# tempPCB.net
KiCad netlist of a schematic drawn in EAGLE
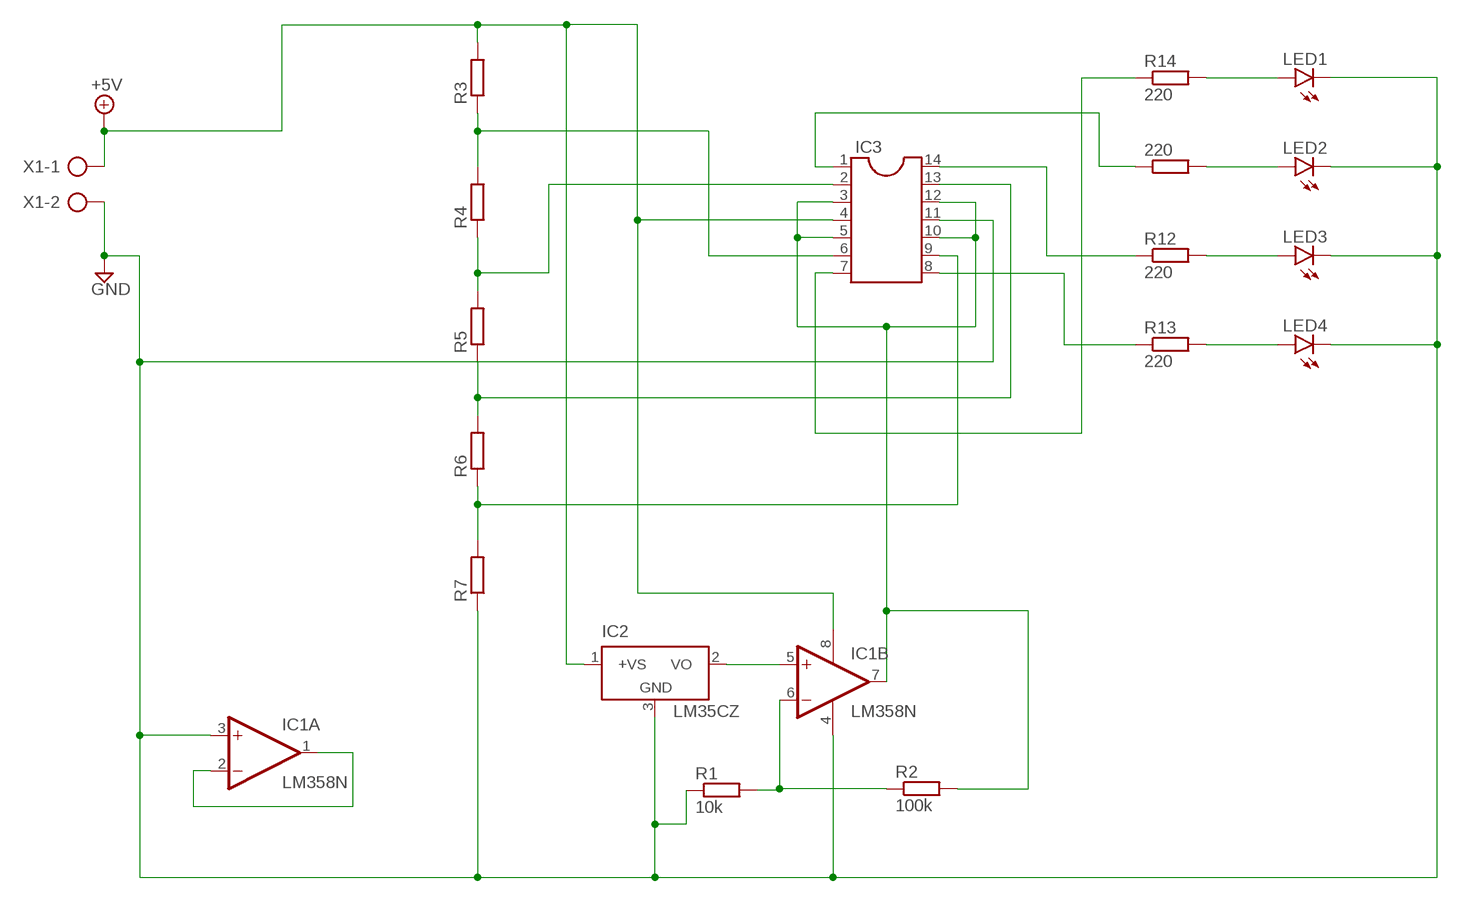
[diagram p0: schematic, sheet 1]

(export (version "E")
  (design (tool "Eeschema 10.0.6"))
  (components
    (comp (ref "220")
      (value "R-EU_0207/10")
      (footprint "eagle-import:0207_10")
      (libsource (lib "eagle-import") (part "R-EU_0207/10"))
    )
    (comp (ref "IC1")
      (value "LM358N")
      (footprint "eagle-import:DIL08")
      (libsource (lib "eagle-import") (part "LM358N"))
    )
    (comp (ref "IC2")
      (value "LM35CZ")
      (footprint "eagle-import:TO92")
      (libsource (lib "eagle-import") (part "LM35CZ"))
    )
    (comp (ref "IC3")
      (value "DIL14")
      (footprint "eagle-import:DIL14")
      (libsource (lib "eagle-import") (part "DIL14"))
    )
    (comp (ref "LED1")
      (value "LED5MM")
      (footprint "eagle-import:LED5MM")
      (libsource (lib "eagle-import") (part "LED5MM"))
    )
    (comp (ref "LED2")
      (value "LED5MM")
      (footprint "eagle-import:LED5MM")
      (libsource (lib "eagle-import") (part "LED5MM"))
    )
    (comp (ref "LED3")
      (value "LED5MM")
      (footprint "eagle-import:LED5MM")
      (libsource (lib "eagle-import") (part "LED5MM"))
    )
    (comp (ref "LED4")
      (value "LED5MM")
      (footprint "eagle-import:LED5MM")
      (libsource (lib "eagle-import") (part "LED5MM"))
    )
    (comp (ref "R1")
      (value "10k")
      (footprint "eagle-import:R1206")
      (libsource (lib "eagle-import") (part "R-EU_R1206"))
    )
    (comp (ref "R2")
      (value "100k")
      (footprint "eagle-import:R1206")
      (libsource (lib "eagle-import") (part "R-EU_R1206"))
    )
    (comp (ref "R3")
      (value "R-EU_R1206")
      (footprint "eagle-import:R1206")
      (libsource (lib "eagle-import") (part "R-EU_R1206"))
    )
    (comp (ref "R4")
      (value "R-EU_0207/10")
      (footprint "eagle-import:0207_10")
      (libsource (lib "eagle-import") (part "R-EU_0207/10"))
    )
    (comp (ref "R5")
      (value "R-EU_R1206")
      (footprint "eagle-import:R1206")
      (libsource (lib "eagle-import") (part "R-EU_R1206"))
    )
    (comp (ref "R6")
      (value "R-EU_0207/10")
      (footprint "eagle-import:0207_10")
      (libsource (lib "eagle-import") (part "R-EU_0207/10"))
    )
    (comp (ref "R7")
      (value "R-EU_R1206")
      (footprint "eagle-import:R1206")
      (libsource (lib "eagle-import") (part "R-EU_R1206"))
    )
    (comp (ref "R12")
      (value "220")
      (footprint "eagle-import:0207_10")
      (libsource (lib "eagle-import") (part "R-EU_0207/10"))
    )
    (comp (ref "R13")
      (value "220")
      (footprint "eagle-import:0207_10")
      (libsource (lib "eagle-import") (part "R-EU_0207/10"))
    )
    (comp (ref "R14")
      (value "220")
      (footprint "eagle-import:0207_10")
      (libsource (lib "eagle-import") (part "R-EU_0207/10"))
    )
    (comp (ref "X1")
      (value "AK500/2")
      (footprint "eagle-import:AK500_2")
      (libsource (lib "eagle-import") (part "AK500/2"))
    )
  )
  (nets
    (net (code "1") (name "+5V") (class "Default")
      (node (ref "IC1") (pin "8") (pinfunction "V+_8") (pintype "power_in"))
      (node (ref "IC2") (pin "1") (pinfunction "+VS_1") (pintype "input"))
      (node (ref "IC3") (pin "4") (pinfunction "4_4") (pintype "passive"))
      (node (ref "R3") (pin "2") (pinfunction "2_2") (pintype "passive"))
      (node (ref "X1") (pin "1") (pinfunction "KL_1") (pintype "passive"))
    )
    (net (code "2") (name "GND") (class "Default")
      (node (ref "IC1") (pin "3") (pinfunction "+IN_3") (pintype "input"))
      (node (ref "IC1") (pin "4") (pinfunction "V-_4") (pintype "power_in"))
      (node (ref "IC2") (pin "3") (pinfunction "GND_3") (pintype "power_in"))
      (node (ref "IC3") (pin "11") (pinfunction "11_11") (pintype "passive"))
      (node (ref "LED1") (pin "K") (pinfunction "C_K") (pintype "passive"))
      (node (ref "LED2") (pin "K") (pinfunction "C_K") (pintype "passive"))
      (node (ref "LED3") (pin "K") (pinfunction "C_K") (pintype "passive"))
      (node (ref "LED4") (pin "K") (pinfunction "C_K") (pintype "passive"))
      (node (ref "R1") (pin "1") (pinfunction "1_1") (pintype "passive"))
      (node (ref "R7") (pin "1") (pinfunction "1_1") (pintype "passive"))
      (node (ref "X1") (pin "2") (pinfunction "KL_2") (pintype "passive"))
    )
    (net (code "3") (name "Net-(220-Pad1)") (class "Default")
      (node (ref "220") (pin "1") (pinfunction "1_1") (pintype "passive"))
      (node (ref "IC3") (pin "1") (pinfunction "1_1") (pintype "passive"))
    )
    (net (code "4") (name "Net-(220-Pad2)") (class "Default")
      (node (ref "220") (pin "2") (pinfunction "2_2") (pintype "passive"))
      (node (ref "LED2") (pin "A") (pinfunction "A_A") (pintype "passive"))
    )
    (net (code "5") (name "Net-(IC1A--IN)") (class "Default")
      (node (ref "IC1") (pin "1") (pinfunction "OUT_1") (pintype "output"))
      (node (ref "IC1") (pin "2") (pinfunction "-IN_2") (pintype "input"))
    )
    (net (code "6") (name "Net-(IC1B-+IN)") (class "Default")
      (node (ref "IC1") (pin "5") (pinfunction "+IN_5") (pintype "input"))
      (node (ref "IC2") (pin "2") (pinfunction "VO_2") (pintype "input"))
    )
    (net (code "7") (name "Net-(IC1B--IN)") (class "Default")
      (node (ref "IC1") (pin "6") (pinfunction "-IN_6") (pintype "input"))
      (node (ref "R1") (pin "2") (pinfunction "2_2") (pintype "passive"))
      (node (ref "R2") (pin "1") (pinfunction "1_1") (pintype "passive"))
    )
    (net (code "8") (name "Net-(IC1B-OUT)") (class "Default")
      (node (ref "IC1") (pin "7") (pinfunction "OUT_7") (pintype "output"))
      (node (ref "IC3") (pin "10") (pinfunction "10_10") (pintype "passive"))
      (node (ref "IC3") (pin "12") (pinfunction "12_12") (pintype "passive"))
      (node (ref "IC3") (pin "3") (pinfunction "3_3") (pintype "passive"))
      (node (ref "IC3") (pin "5") (pinfunction "5_5") (pintype "passive"))
      (node (ref "R2") (pin "2") (pinfunction "2_2") (pintype "passive"))
    )
    (net (code "9") (name "Net-(IC3-Pad2)") (class "Default")
      (node (ref "IC3") (pin "2") (pinfunction "2_2") (pintype "passive"))
      (node (ref "R4") (pin "1") (pinfunction "1_1") (pintype "passive"))
      (node (ref "R5") (pin "2") (pinfunction "2_2") (pintype "passive"))
    )
    (net (code "10") (name "Net-(IC3-Pad6)") (class "Default")
      (node (ref "IC3") (pin "6") (pinfunction "6_6") (pintype "passive"))
      (node (ref "R3") (pin "1") (pinfunction "1_1") (pintype "passive"))
      (node (ref "R4") (pin "2") (pinfunction "2_2") (pintype "passive"))
    )
    (net (code "11") (name "Net-(IC3-Pad7)") (class "Default")
      (node (ref "IC3") (pin "7") (pinfunction "7_7") (pintype "passive"))
      (node (ref "R14") (pin "1") (pinfunction "1_1") (pintype "passive"))
    )
    (net (code "12") (name "Net-(IC3-Pad8)") (class "Default")
      (node (ref "IC3") (pin "8") (pinfunction "8_8") (pintype "passive"))
      (node (ref "R13") (pin "1") (pinfunction "1_1") (pintype "passive"))
    )
    (net (code "13") (name "Net-(IC3-Pad9)") (class "Default")
      (node (ref "IC3") (pin "9") (pinfunction "9_9") (pintype "passive"))
      (node (ref "R6") (pin "1") (pinfunction "1_1") (pintype "passive"))
      (node (ref "R7") (pin "2") (pinfunction "2_2") (pintype "passive"))
    )
    (net (code "14") (name "Net-(IC3-Pad13)") (class "Default")
      (node (ref "IC3") (pin "13") (pinfunction "13_13") (pintype "passive"))
      (node (ref "R5") (pin "1") (pinfunction "1_1") (pintype "passive"))
      (node (ref "R6") (pin "2") (pinfunction "2_2") (pintype "passive"))
    )
    (net (code "15") (name "Net-(IC3-Pad14)") (class "Default")
      (node (ref "IC3") (pin "14") (pinfunction "14_14") (pintype "passive"))
      (node (ref "R12") (pin "1") (pinfunction "1_1") (pintype "passive"))
    )
    (net (code "16") (name "Net-(LED1-PadA)") (class "Default")
      (node (ref "LED1") (pin "A") (pinfunction "A_A") (pintype "passive"))
      (node (ref "R14") (pin "2") (pinfunction "2_2") (pintype "passive"))
    )
    (net (code "17") (name "Net-(LED3-PadA)") (class "Default")
      (node (ref "LED3") (pin "A") (pinfunction "A_A") (pintype "passive"))
      (node (ref "R12") (pin "2") (pinfunction "2_2") (pintype "passive"))
    )
    (net (code "18") (name "Net-(LED4-PadA)") (class "Default")
      (node (ref "LED4") (pin "A") (pinfunction "A_A") (pintype "passive"))
      (node (ref "R13") (pin "2") (pinfunction "2_2") (pintype "passive"))
    )
  )
)
